# ID5.net
KiCad netlist of a schematic drawn in Altium Designer
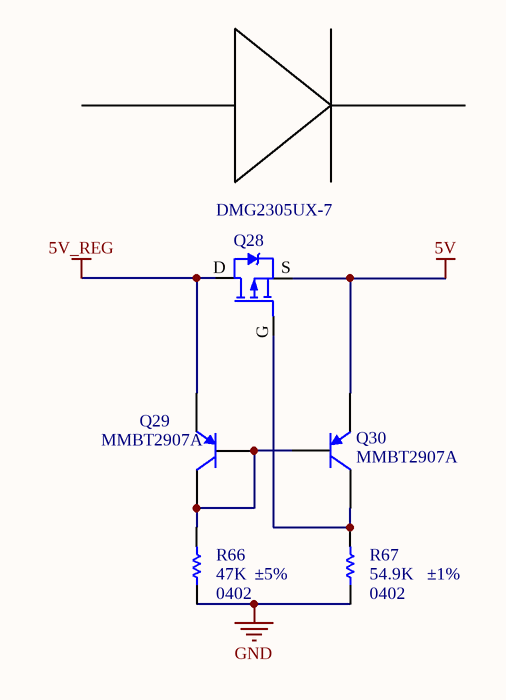
[diagram p0: ID5.SchDoc]

(export (version "E")
  (design (tool "Eeschema 10.0.6"))
  (components
    (comp (ref "Q28")
      (value "DMG2305UX")
      (footprint "DMG2305UX-7")
      (description "MOSFET P-CH 20V 4.2A SOT23")
      (fields
        (field (name "MANUFACTURER") "Diodes Incorporated")
        (field (name "MANUFACTURER PART NUMBER") "DMG2305UX-7")
        (field (name "CREATOR") "osman")
      )
      (libsource (lib "OLogic-Trans-Drivers") (part "DMG2305UX"))
    )
    (comp (ref "Q29")
      (value "MMBT2907A")
      (footprint "SOT23")
      (description "PNP General Purpose Amplifier")
      (fields (field (name "MANUFACTURER") "Fairchild Semiconductor"))
      (libsource (lib "OLogic-Trans-Drivers") (part "MMBT2907A"))
    )
    (comp (ref "Q30")
      (value "MMBT2907A")
      (footprint "SOT23")
      (description "PNP General Purpose Amplifier")
      (fields (field (name "MANUFACTURER") "Fairchild Semiconductor"))
      (libsource (lib "OLogic-Trans-Drivers") (part "MMBT2907A"))
    )
    (comp (ref "R66")
      (value "47K")
      (footprint "RESC0402(1005)_N")
      (description "47K 0402")
      (fields
        (field (name "MANUFACTURER") "Panasonic Electronic Components")
        (field (name "MANUFACTURER PART NUMBER") "ERJ-2GEJ473X")
        (field (name "TOLERANCE") "±5%")
        (field (name "SUPPLIER DEVICE PACKAGE") "0402")
      )
      (libsource (lib "OLogic-Passive") (part "RES 47K OHM 5% 1/10W 0402"))
    )
    (comp (ref "R67")
      (value "54.9K")
      (footprint "RESC0402(1005)_N")
      (description "54.9K 1% 0402")
      (fields
        (field (name "MANUFACTURER") "Panasonic Electronic Components")
        (field (name "MANUFACTURER PART NUMBER") "ERJ-2RKF5492X")
        (field (name "TOLERANCE") "±1%")
        (field (name "SUPPLIER DEVICE PACKAGE") "0402")
      )
      (libsource (lib "OLogic-Passive") (part "RES 54.9K OHM 1% 1/10W 0402"))
    )
  )
  (nets
    (net (code "1") (name "5V") (class "Default")
      (node (ref "Q28") (pin "S") (pinfunction "S_S") (pintype "passive"))
      (node (ref "Q30") (pin "2") (pinfunction "E_2") (pintype "passive"))
    )
    (net (code "2") (name "5V_REG") (class "Default")
      (node (ref "Q28") (pin "D") (pinfunction "D_D") (pintype "passive"))
      (node (ref "Q29") (pin "2") (pinfunction "E_2") (pintype "passive"))
    )
    (net (code "3") (name "GND") (class "Default")
      (node (ref "R66") (pin "1") (pinfunction "1_1") (pintype "passive"))
      (node (ref "R67") (pin "1") (pinfunction "1_1") (pintype "passive"))
    )
    (net (code "4") (name "Net-(Q29-B)") (class "Default")
      (node (ref "Q29") (pin "1") (pinfunction "B_1") (pintype "passive"))
      (node (ref "Q29") (pin "3") (pinfunction "C_3") (pintype "passive"))
      (node (ref "Q30") (pin "1") (pinfunction "B_1") (pintype "passive"))
      (node (ref "R66") (pin "2") (pinfunction "2_2") (pintype "passive"))
    )
    (net (code "5") (name "Net-(Q30-C)") (class "Default")
      (node (ref "Q28") (pin "G") (pinfunction "G_G") (pintype "passive"))
      (node (ref "Q30") (pin "3") (pinfunction "C_3") (pintype "passive"))
      (node (ref "R67") (pin "2") (pinfunction "2_2") (pintype "passive"))
    )
  )
)
